# AquaMate.net
KiCad netlist of a schematic drawn in Altium Designer
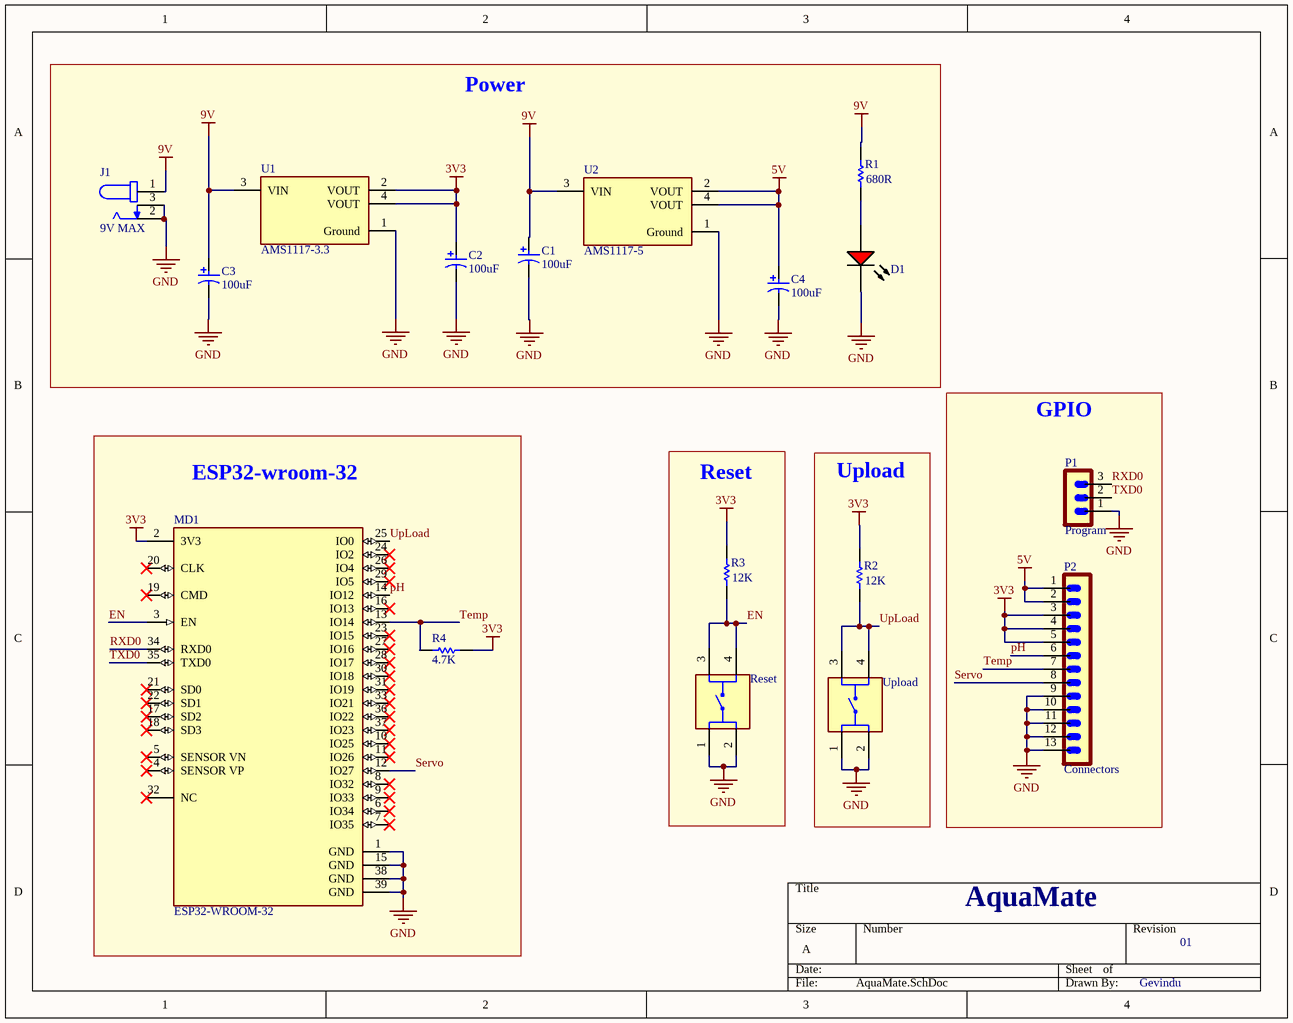
[diagram p0: AquaMate.SchDoc]

(export (version "E")
  (design (tool "Eeschema 10.0.6"))
  (components
    (comp (ref "C1")
      (value "ECA1HM101")
      (footprint "CAPPR65-350-1150X800X1250")
      (description "Aluminum Electrolytic Capacitor, 100 uF, +/- 20%, 50 V, -40 to 85 degC, 2-Pin THD, RoHS, Bulk")
      (fields
        (field (name "MANUFACTURER") "Panasonic")
        (field (name "VOLTAGE") "50V")
        (field (name "CAPACITANCE") "100uF")
      )
      (libsource (lib "Altium Content Vault") (part "CAP-P-2"))
    )
    (comp (ref "C2")
      (value "ECA1HM101")
      (footprint "CAPPR65-350-1150X800X1250")
      (description "Aluminum Electrolytic Capacitor, 100 uF, +/- 20%, 50 V, -40 to 85 degC, 2-Pin THD, RoHS, Bulk")
      (fields
        (field (name "MANUFACTURER") "Panasonic")
        (field (name "VOLTAGE") "50V")
        (field (name "CAPACITANCE") "100uF")
      )
      (libsource (lib "Altium Content Vault") (part "CAP-P-2"))
    )
    (comp (ref "C3")
      (value "ECA1HM101")
      (footprint "CAPPR65-350-1150X800X1250")
      (description "Aluminum Electrolytic Capacitor, 100 uF, +/- 20%, 50 V, -40 to 85 degC, 2-Pin THD, RoHS, Bulk")
      (fields
        (field (name "MANUFACTURER") "Panasonic")
        (field (name "VOLTAGE") "50V")
        (field (name "CAPACITANCE") "100uF")
      )
      (libsource (lib "Altium Content Vault") (part "CAP-P-2"))
    )
    (comp (ref "C4")
      (value "ECA1HM101")
      (footprint "CAPPR65-350-1150X800X1250")
      (description "Aluminum Electrolytic Capacitor, 100 uF, +/- 20%, 50 V, -40 to 85 degC, 2-Pin THD, RoHS, Bulk")
      (fields
        (field (name "MANUFACTURER") "Panasonic")
        (field (name "VOLTAGE") "50V")
        (field (name "CAPACITANCE") "100uF")
      )
      (libsource (lib "Altium Content Vault") (part "CAP-P-2"))
    )
    (comp (ref "D1")
      (value "WP7113SRD/D")
      (footprint "KING-WP7113SRDD_V")
      (description "The Super Bright Red Source Color Device, 1.85 V, -40 to 85 degC, 2-Pin THD, RoHS, Tape and Reel")
      (libsource (lib "Altium Content Vault") (part "LED-RED-AK-2"))
    )
    (comp (ref "J1")
      (value "9V MAX")
      (footprint "CUI_PJ-102A")
      (description "2.0 mm Center Pin, 2.5 A, Right Angle, Through Hole, Tapered Pins, Dc Power Jack Connector")
      (fields (field (name "MP") "PJ-102A"))
      (libsource (lib "PJ-102A") (part "PJ-102A"))
    )
    (comp (ref "MD1")
      (value "ESP32-WROOM-32")
      (footprint "FP-ESP32-WROOM-32-MFG")
      (description "RX TXRX MOD WIFI SURFACE MOUNT")
      (libsource (lib "Altium Content Vault") (part "ee866abf0b6c51247b7f5cdebf2f250"))
    )
    (comp (ref "P1")
      (value "Program")
      (footprint "B3B-PH-K")
      (description "Connector Header Through Hole 3 position 0.079 (2.00mm)")
      (fields (field (name "MP") "B3B-PH-K") (field (name "MF") "JST"))
      (libsource (lib "B3B-PH-K") (part "B3B-PH-K"))
    )
    (comp (ref "P2")
      (value "Connectors")
      (footprint "B13B-PH-K")
      (description "Connector Header Through Hole 13 position 0.079 (2.00mm)")
      (fields (field (name "MF") "JST") (field (name "MP") "B13B-PH-K"))
      (libsource (lib "B13B-PH-K") (part "B13B-PH-K"))
    )
    (comp (ref "R1")
      (value "680R")
      (footprint "AXIAL-0.3")
      (description "Resistor")
      (fields (field (name "Comment") "Res1") (field (name "PUBLISHER") "Altium Limited"))
      (libsource (lib "Miscellaneous Devices") (part "Res1"))
    )
    (comp (ref "R2")
      (value "12K")
      (footprint "AXIAL-0.3")
      (description "Resistor")
      (fields (field (name "Comment") "Res1") (field (name "PUBLISHER") "Altium Limited"))
      (libsource (lib "Miscellaneous Devices") (part "Res1"))
    )
    (comp (ref "R3")
      (value "12K")
      (footprint "AXIAL-0.3")
      (description "Resistor")
      (fields (field (name "Comment") "Res1") (field (name "PUBLISHER") "Altium Limited"))
      (libsource (lib "Miscellaneous Devices") (part "Res1"))
    )
    (comp (ref "R4")
      (value "4.7K")
      (footprint "AXIAL-0.3")
      (description "Resistor")
      (fields (field (name "Comment") "Res1") (field (name "PUBLISHER") "Altium Limited"))
      (libsource (lib "Miscellaneous Devices") (part "Res1"))
    )
    (comp (ref "Reset")
      (value "1825910-6")
      (footprint "SW_1825910-6-4")
      (description "Switch Tactile OFF (ON) SPST Round Button PC Pins 0.05A 24VDC 100000Cycles 1.57N Thru-Hole Loose")
      (libsource (lib "1825910-6") (part "1825910-6"))
    )
    (comp (ref "U1")
      (value "AMS1117-3.3")
      (footprint "FP-AMS1117-IPC_C")
      (description "LDO Voltage Regulators 1A, 3.3V")
      (fields
        (field (name "OCTOPART") "https://octopart.com/ams1117-3.3-advanced+monolithic+systems-25899300")
        (field (name "MANUFACTURER") "Advanced Monolithic Systems")
      )
      (libsource (lib "Altium Content Vault") (part "8bdbb5f8e77002000e30dd2845d0354"))
    )
    (comp (ref "U2")
      (value "AMS1117-5")
      (footprint "FP-AMS1117-IPC_C")
      (description "LDO Voltage Regulators 1A, 5V")
      (fields
        (field (name "MANUFACTURER PART NUMBER") "AMS1117-3.3")
        (field (name "OCTOPART") "https://octopart.com/ams1117-3.3-advanced+monolithic+systems-25899300")
      )
      (libsource (lib "Altium Content Vault") (part "8bdbb5f8e77002000e30dd2845d0354"))
    )
    (comp (ref "Upload")
      (value "1825910-6")
      (footprint "SW_1825910-6-4")
      (description "Switch Tactile OFF (ON) SPST Round Button PC Pins 0.05A 24VDC 100000Cycles 1.57N Thru-Hole Loose")
      (libsource (lib "1825910-6") (part "1825910-6"))
    )
  )
  (nets
    (net (code "1") (name "/EN") (class "Default")
      (node (ref "MD1") (pin "3") (pinfunction "EN_3") (pintype "input"))
      (node (ref "R3") (pin "1") (pinfunction "1_1") (pintype "passive"))
      (node (ref "Reset") (pin "3") (pinfunction "3_3") (pintype "passive"))
      (node (ref "Reset") (pin "4") (pinfunction "4_4") (pintype "passive"))
    )
    (net (code "2") (name "/RXD0") (class "Default")
      (node (ref "MD1") (pin "34") (pinfunction "RXD0_34") (pintype "bidirectional"))
      (node (ref "P1") (pin "3") (pinfunction "3_3") (pintype "passive"))
    )
    (net (code "3") (name "/Servo") (class "Default")
      (node (ref "MD1") (pin "12") (pinfunction "IO27_12") (pintype "bidirectional"))
      (node (ref "P2") (pin "8") (pinfunction "8_8") (pintype "passive"))
    )
    (net (code "4") (name "/TXD0") (class "Default")
      (node (ref "MD1") (pin "35") (pinfunction "TXD0_35") (pintype "bidirectional"))
      (node (ref "P1") (pin "2") (pinfunction "2_2") (pintype "passive"))
    )
    (net (code "5") (name "/Temp") (class "Default")
      (node (ref "MD1") (pin "13") (pinfunction "IO14_13") (pintype "bidirectional"))
      (node (ref "P2") (pin "7") (pinfunction "7_7") (pintype "passive"))
      (node (ref "R4") (pin "2") (pinfunction "2_2") (pintype "passive"))
    )
    (net (code "6") (name "/UpLoad") (class "Default")
      (node (ref "MD1") (pin "25") (pinfunction "IO0_25") (pintype "bidirectional"))
      (node (ref "R2") (pin "1") (pinfunction "1_1") (pintype "passive"))
      (node (ref "Upload") (pin "3") (pinfunction "3_3") (pintype "passive"))
      (node (ref "Upload") (pin "4") (pinfunction "4_4") (pintype "passive"))
    )
    (net (code "7") (name "/pH") (class "Default")
      (node (ref "MD1") (pin "14") (pinfunction "IO12_14") (pintype "bidirectional"))
      (node (ref "P2") (pin "6") (pinfunction "6_6") (pintype "passive"))
    )
    (net (code "8") (name "3V3") (class "Default")
      (node (ref "C2") (pin "1") (pinfunction "1_1") (pintype "passive"))
      (node (ref "MD1") (pin "2") (pinfunction "3V3_2") (pintype "power_in"))
      (node (ref "P2") (pin "3") (pinfunction "3_3") (pintype "passive"))
      (node (ref "P2") (pin "4") (pinfunction "4_4") (pintype "passive"))
      (node (ref "P2") (pin "5") (pinfunction "5_5") (pintype "passive"))
      (node (ref "R2") (pin "2") (pinfunction "2_2") (pintype "passive"))
      (node (ref "R3") (pin "2") (pinfunction "2_2") (pintype "passive"))
      (node (ref "R4") (pin "1") (pinfunction "1_1") (pintype "passive"))
      (node (ref "U1") (pin "2") (pinfunction "VOUT_2") (pintype "passive"))
      (node (ref "U1") (pin "4") (pinfunction "VOUT_4") (pintype "passive"))
    )
    (net (code "9") (name "5V") (class "Default")
      (node (ref "C4") (pin "1") (pinfunction "1_1") (pintype "passive"))
      (node (ref "P2") (pin "1") (pinfunction "1_1") (pintype "passive"))
      (node (ref "P2") (pin "2") (pinfunction "2_2") (pintype "passive"))
      (node (ref "U2") (pin "2") (pinfunction "VOUT_2") (pintype "passive"))
      (node (ref "U2") (pin "4") (pinfunction "VOUT_4") (pintype "passive"))
    )
    (net (code "10") (name "9V") (class "Default")
      (node (ref "C1") (pin "1") (pinfunction "1_1") (pintype "passive"))
      (node (ref "C3") (pin "1") (pinfunction "1_1") (pintype "passive"))
      (node (ref "J1") (pin "1") (pinfunction "1_1") (pintype "passive"))
      (node (ref "R1") (pin "2") (pinfunction "2_2") (pintype "passive"))
      (node (ref "U1") (pin "3") (pinfunction "VIN_3") (pintype "power_in"))
      (node (ref "U2") (pin "3") (pinfunction "VIN_3") (pintype "power_in"))
    )
    (net (code "11") (name "GND") (class "Default")
      (node (ref "C1") (pin "2") (pinfunction "2_2") (pintype "passive"))
      (node (ref "C2") (pin "2") (pinfunction "2_2") (pintype "passive"))
      (node (ref "C3") (pin "2") (pinfunction "2_2") (pintype "passive"))
      (node (ref "C4") (pin "2") (pinfunction "2_2") (pintype "passive"))
      (node (ref "D1") (pin "2") (pinfunction "K_2") (pintype "passive"))
      (node (ref "J1") (pin "2") (pinfunction "2_2") (pintype "passive"))
      (node (ref "J1") (pin "3") (pinfunction "3_3") (pintype "passive"))
      (node (ref "MD1") (pin "1") (pinfunction "GND_1") (pintype "power_in"))
      (node (ref "MD1") (pin "15") (pinfunction "GND_15") (pintype "power_in"))
      (node (ref "MD1") (pin "38") (pinfunction "GND_38") (pintype "power_in"))
      (node (ref "MD1") (pin "39") (pinfunction "GND_39") (pintype "power_in"))
      (node (ref "P1") (pin "1") (pinfunction "1_1") (pintype "passive"))
      (node (ref "P2") (pin "10") (pinfunction "10_10") (pintype "passive"))
      (node (ref "P2") (pin "11") (pinfunction "11_11") (pintype "passive"))
      (node (ref "P2") (pin "12") (pinfunction "12_12") (pintype "passive"))
      (node (ref "P2") (pin "13") (pinfunction "13_13") (pintype "passive"))
      (node (ref "P2") (pin "9") (pinfunction "9_9") (pintype "passive"))
      (node (ref "Reset") (pin "1") (pinfunction "1_1") (pintype "passive"))
      (node (ref "Reset") (pin "2") (pinfunction "2_2") (pintype "passive"))
      (node (ref "U1") (pin "1") (pinfunction "Ground_1") (pintype "power_in"))
      (node (ref "U2") (pin "1") (pinfunction "Ground_1") (pintype "power_in"))
      (node (ref "Upload") (pin "1") (pinfunction "1_1") (pintype "passive"))
      (node (ref "Upload") (pin "2") (pinfunction "2_2") (pintype "passive"))
    )
    (net (code "12") (name "Net-(D1-A)") (class "Default")
      (node (ref "D1") (pin "1") (pinfunction "A_1") (pintype "passive"))
      (node (ref "R1") (pin "1") (pinfunction "1_1") (pintype "passive"))
    )
    (net (code "13") (name "unconnected-(MD1-CLK-Pad20)") (class "Default")
      (node (ref "MD1") (pin "20") (pinfunction "CLK_20") (pintype "bidirectional+no_connect"))
    )
    (net (code "14") (name "unconnected-(MD1-CMD-Pad19)") (class "Default")
      (node (ref "MD1") (pin "19") (pinfunction "CMD_19") (pintype "bidirectional+no_connect"))
    )
    (net (code "15") (name "unconnected-(MD1-IO2-Pad24)") (class "Default")
      (node (ref "MD1") (pin "24") (pinfunction "IO2_24") (pintype "bidirectional+no_connect"))
    )
    (net (code "16") (name "unconnected-(MD1-IO4-Pad26)") (class "Default")
      (node (ref "MD1") (pin "26") (pinfunction "IO4_26") (pintype "bidirectional+no_connect"))
    )
    (net (code "17") (name "unconnected-(MD1-IO5-Pad29)") (class "Default")
      (node (ref "MD1") (pin "29") (pinfunction "IO5_29") (pintype "bidirectional+no_connect"))
    )
    (net (code "18") (name "unconnected-(MD1-IO13-Pad16)") (class "Default")
      (node (ref "MD1") (pin "16") (pinfunction "IO13_16") (pintype "bidirectional+no_connect"))
    )
    (net (code "19") (name "unconnected-(MD1-IO15-Pad23)") (class "Default")
      (node (ref "MD1") (pin "23") (pinfunction "IO15_23") (pintype "bidirectional+no_connect"))
    )
    (net (code "20") (name "unconnected-(MD1-IO16-Pad27)") (class "Default")
      (node (ref "MD1") (pin "27") (pinfunction "IO16_27") (pintype "bidirectional+no_connect"))
    )
    (net (code "21") (name "unconnected-(MD1-IO17-Pad28)") (class "Default")
      (node (ref "MD1") (pin "28") (pinfunction "IO17_28") (pintype "bidirectional+no_connect"))
    )
    (net (code "22") (name "unconnected-(MD1-IO18-Pad30)") (class "Default")
      (node (ref "MD1") (pin "30") (pinfunction "IO18_30") (pintype "bidirectional+no_connect"))
    )
    (net (code "23") (name "unconnected-(MD1-IO19-Pad31)") (class "Default")
      (node (ref "MD1") (pin "31") (pinfunction "IO19_31") (pintype "bidirectional+no_connect"))
    )
    (net (code "24") (name "unconnected-(MD1-IO21-Pad33)") (class "Default")
      (node (ref "MD1") (pin "33") (pinfunction "IO21_33") (pintype "bidirectional+no_connect"))
    )
    (net (code "25") (name "unconnected-(MD1-IO22-Pad36)") (class "Default")
      (node (ref "MD1") (pin "36") (pinfunction "IO22_36") (pintype "bidirectional+no_connect"))
    )
    (net (code "26") (name "unconnected-(MD1-IO23-Pad37)") (class "Default")
      (node (ref "MD1") (pin "37") (pinfunction "IO23_37") (pintype "bidirectional+no_connect"))
    )
    (net (code "27") (name "unconnected-(MD1-IO25-Pad10)") (class "Default")
      (node (ref "MD1") (pin "10") (pinfunction "IO25_10") (pintype "bidirectional+no_connect"))
    )
    (net (code "28") (name "unconnected-(MD1-IO26-Pad11)") (class "Default")
      (node (ref "MD1") (pin "11") (pinfunction "IO26_11") (pintype "bidirectional+no_connect"))
    )
    (net (code "29") (name "unconnected-(MD1-IO32-Pad8)") (class "Default")
      (node (ref "MD1") (pin "8") (pinfunction "IO32_8") (pintype "bidirectional+no_connect"))
    )
    (net (code "30") (name "unconnected-(MD1-IO33-Pad9)") (class "Default")
      (node (ref "MD1") (pin "9") (pinfunction "IO33_9") (pintype "bidirectional+no_connect"))
    )
    (net (code "31") (name "unconnected-(MD1-IO34-Pad6)") (class "Default")
      (node (ref "MD1") (pin "6") (pinfunction "IO34_6") (pintype "bidirectional+no_connect"))
    )
    (net (code "32") (name "unconnected-(MD1-IO35-Pad7)") (class "Default")
      (node (ref "MD1") (pin "7") (pinfunction "IO35_7") (pintype "bidirectional+no_connect"))
    )
    (net (code "33") (name "unconnected-(MD1-NC-Pad32)") (class "Default")
      (node (ref "MD1") (pin "32") (pinfunction "NC_32") (pintype "passive+no_connect"))
    )
    (net (code "34") (name "unconnected-(MD1-SD0-Pad21)") (class "Default")
      (node (ref "MD1") (pin "21") (pinfunction "SD0_21") (pintype "bidirectional+no_connect"))
    )
    (net (code "35") (name "unconnected-(MD1-SD1-Pad22)") (class "Default")
      (node (ref "MD1") (pin "22") (pinfunction "SD1_22") (pintype "bidirectional+no_connect"))
    )
    (net (code "36") (name "unconnected-(MD1-SD2-Pad17)") (class "Default")
      (node (ref "MD1") (pin "17") (pinfunction "SD2_17") (pintype "bidirectional+no_connect"))
    )
    (net (code "37") (name "unconnected-(MD1-SD3-Pad18)") (class "Default")
      (node (ref "MD1") (pin "18") (pinfunction "SD3_18") (pintype "bidirectional+no_connect"))
    )
    (net (code "38") (name "unconnected-(MD1-SENSOR_VN-Pad5)") (class "Default")
      (node (ref "MD1") (pin "5") (pinfunction "SENSOR_VN_5") (pintype "bidirectional+no_connect"))
    )
    (net (code "39") (name "unconnected-(MD1-SENSOR_VP-Pad4)") (class "Default")
      (node (ref "MD1") (pin "4") (pinfunction "SENSOR_VP_4") (pintype "bidirectional+no_connect"))
    )
  )
)
